# RS232.net
KiCad netlist of a schematic drawn in Altium Designer
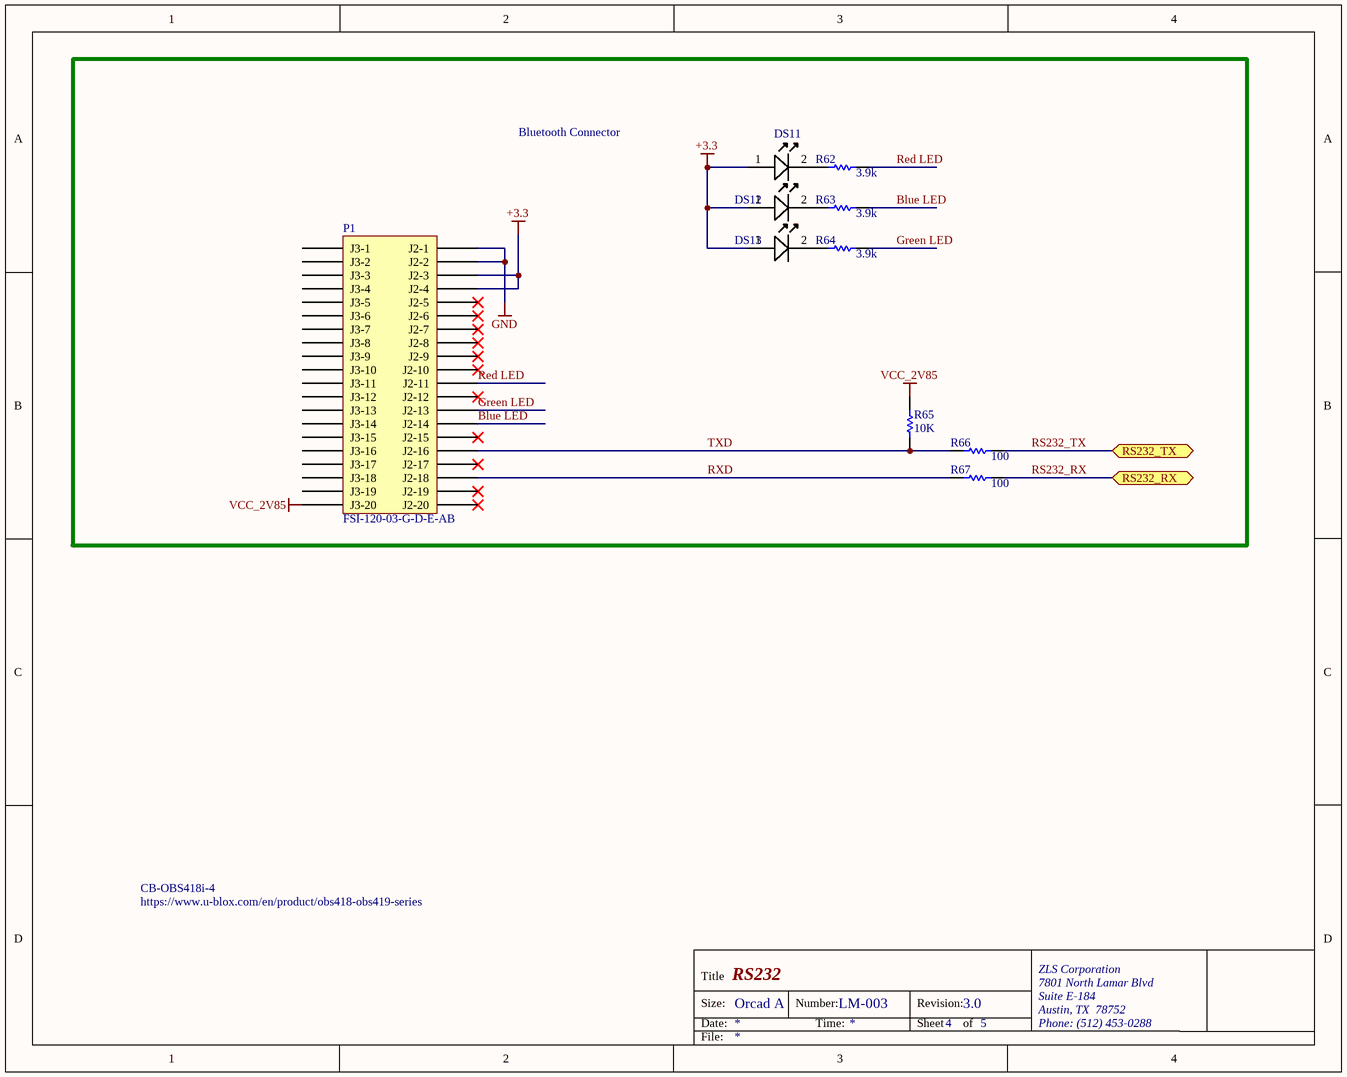
[diagram p0: RS232.SchDoc]

(export (version "E")
  (design (tool "Eeschema 10.0.6"))
  (components
    (comp (ref "DS11")
      (value "Lite-On LTST-S220KGKT Green LED, 571 nm 2012 (0805) Side View, Rectangle Lens SMD package")
      (footprint "0805C_L")
      (fields
        (field (name "MANUFACTURER") "Vishay / Lite-On")
        (field (name "MANUFACTURER PART NUMBER") "LTST-S220KGKT")
      )
      (libsource (lib "*") (part "LED A/K"))
    )
    (comp (ref "DS12")
      (value "Lite-On LTST-S220KGKT Green LED, 571 nm 2012 (0805) Side View, Rectangle Lens SMD package")
      (footprint "0805C_L")
      (fields
        (field (name "MANUFACTURER") "Vishay / Lite-On")
        (field (name "MANUFACTURER PART NUMBER") "LTST-S220KGKT")
      )
      (libsource (lib "*") (part "LED A/K"))
    )
    (comp (ref "DS13")
      (value "Lite-On LTST-S220KGKT Green LED, 571 nm 2012 (0805) Side View, Rectangle Lens SMD package")
      (footprint "0805C_L")
      (fields
        (field (name "MANUFACTURER") "Vishay / Lite-On")
        (field (name "MANUFACTURER PART NUMBER") "LTST-S220KGKT")
      )
      (libsource (lib "*") (part "LED A/K"))
    )
    (comp (ref "P1")
      (value "FSI-120-03-G-D-E-AB")
      (footprint "FSI-120-03-G-D-E-AB")
      (fields (field (name "SUPPLIER PART NUMBER 1") "FSI-120-03-G-D-E-AB"))
      (libsource (lib "ZLS_Schematic_lib") (part "FSI-120-03-G-D-E-AB"))
    )
    (comp (ref "R62")
      (value "3.9k")
      (footprint "RESC0805(2012)_L")
      (description "2R55 0.125W 1% 0805 (2012 Metric)  SMD")
      (fields (field (name "TOLERANCE") "1 %") (field (name "POWER") "0.125 W"))
      (libsource (lib "Altium Content Vault") (part "CMP-1013-00215-1"))
    )
    (comp (ref "R63")
      (value "3.9k")
      (footprint "RESC0805(2012)_L")
      (description "2R55 0.125W 1% 0805 (2012 Metric)  SMD")
      (fields (field (name "TOLERANCE") "1 %") (field (name "POWER") "0.125 W"))
      (libsource (lib "Altium Content Vault") (part "CMP-1013-00215-1"))
    )
    (comp (ref "R64")
      (value "3.9k")
      (footprint "RESC0805(2012)_L")
      (description "2R55 0.125W 1% 0805 (2012 Metric)  SMD")
      (fields (field (name "TOLERANCE") "1 %") (field (name "POWER") "0.125 W"))
      (libsource (lib "Altium Content Vault") (part "CMP-1013-00215-1"))
    )
    (comp (ref "R65")
      (value "10K")
      (footprint "RESC0805(2012)_L")
      (description "2R55 0.125W 1% 0805 (2012 Metric)  SMD")
      (fields (field (name "TOLERANCE") "1 %") (field (name "POWER") "0.125 W"))
      (libsource (lib "Altium Content Vault") (part "CMP-1013-00215-1"))
    )
    (comp (ref "R66")
      (value "100")
      (footprint "RESC0805(2012)_L")
      (description "2R55 0.125W 1% 0805 (2012 Metric)  SMD")
      (fields (field (name "TOLERANCE") "1 %") (field (name "POWER") "0.125 W"))
      (libsource (lib "Altium Content Vault") (part "CMP-1013-00215-1"))
    )
    (comp (ref "R67")
      (value "100")
      (footprint "RESC0805(2012)_L")
      (description "2R55 0.125W 1% 0805 (2012 Metric)  SMD")
      (fields (field (name "TOLERANCE") "1 %") (field (name "POWER") "0.125 W"))
      (libsource (lib "Altium Content Vault") (part "CMP-1013-00215-1"))
    )
  )
  (nets
    (net (code "1") (name "+3.3") (class "Default")
      (node (ref "DS11") (pin "1") (pinfunction "A_1") (pintype "passive"))
      (node (ref "DS12") (pin "1") (pinfunction "A_1") (pintype "passive"))
      (node (ref "DS13") (pin "1") (pinfunction "A_1") (pintype "passive"))
      (node (ref "P1") (pin "J2-3") (pinfunction "J2-3_J2-3") (pintype "passive"))
      (node (ref "P1") (pin "J2-4") (pinfunction "J2-4_J2-4") (pintype "passive"))
    )
    (net (code "2") (name "/Blue LED") (class "Default")
      (node (ref "P1") (pin "J2-14") (pinfunction "J2-14_J2-14") (pintype "passive"))
      (node (ref "R63") (pin "1") (pinfunction "1_1") (pintype "passive"))
    )
    (net (code "3") (name "/Green LED") (class "Default")
      (node (ref "P1") (pin "J2-13") (pinfunction "J2-13_J2-13") (pintype "passive"))
      (node (ref "R64") (pin "1") (pinfunction "1_1") (pintype "passive"))
    )
    (net (code "4") (name "/RS232_RX") (class "Default")
      (node (ref "R67") (pin "1") (pinfunction "1_1") (pintype "passive"))
    )
    (net (code "5") (name "/RS232_TX") (class "Default")
      (node (ref "R66") (pin "1") (pinfunction "1_1") (pintype "passive"))
    )
    (net (code "6") (name "/RXD") (class "Default")
      (node (ref "P1") (pin "J2-18") (pinfunction "J2-18_J2-18") (pintype "passive"))
      (node (ref "R67") (pin "2") (pinfunction "2_2") (pintype "passive"))
    )
    (net (code "7") (name "/Red LED") (class "Default")
      (node (ref "P1") (pin "J2-11") (pinfunction "J2-11_J2-11") (pintype "passive"))
      (node (ref "R62") (pin "1") (pinfunction "1_1") (pintype "passive"))
    )
    (net (code "8") (name "/TXD") (class "Default")
      (node (ref "P1") (pin "J2-16") (pinfunction "J2-16_J2-16") (pintype "passive"))
      (node (ref "R65") (pin "2") (pinfunction "2_2") (pintype "passive"))
      (node (ref "R66") (pin "2") (pinfunction "2_2") (pintype "passive"))
    )
    (net (code "9") (name "GND") (class "Default")
      (node (ref "P1") (pin "J2-1") (pinfunction "J2-1_J2-1") (pintype "passive"))
      (node (ref "P1") (pin "J2-2") (pinfunction "J2-2_J2-2") (pintype "passive"))
    )
    (net (code "10") (name "Net-(DS11-K)") (class "Default")
      (node (ref "DS11") (pin "2") (pinfunction "K_2") (pintype "passive"))
      (node (ref "R62") (pin "2") (pinfunction "2_2") (pintype "passive"))
    )
    (net (code "11") (name "Net-(DS12-K)") (class "Default")
      (node (ref "DS12") (pin "2") (pinfunction "K_2") (pintype "passive"))
      (node (ref "R63") (pin "2") (pinfunction "2_2") (pintype "passive"))
    )
    (net (code "12") (name "Net-(DS13-K)") (class "Default")
      (node (ref "DS13") (pin "2") (pinfunction "K_2") (pintype "passive"))
      (node (ref "R64") (pin "2") (pinfunction "2_2") (pintype "passive"))
    )
    (net (code "13") (name "VCC_2V85") (class "Default")
      (node (ref "P1") (pin "J3-20") (pinfunction "J3-20_J3-20") (pintype "passive"))
      (node (ref "R65") (pin "1") (pinfunction "1_1") (pintype "passive"))
    )
    (net (code "14") (name "unconnected-(P1-PadJ2-5)") (class "Default")
      (node (ref "P1") (pin "J2-5") (pinfunction "J2-5_J2-5") (pintype "passive+no_connect"))
    )
    (net (code "15") (name "unconnected-(P1-PadJ2-6)") (class "Default")
      (node (ref "P1") (pin "J2-6") (pinfunction "J2-6_J2-6") (pintype "passive+no_connect"))
    )
    (net (code "16") (name "unconnected-(P1-PadJ2-7)") (class "Default")
      (node (ref "P1") (pin "J2-7") (pinfunction "J2-7_J2-7") (pintype "passive+no_connect"))
    )
    (net (code "17") (name "unconnected-(P1-PadJ2-8)") (class "Default")
      (node (ref "P1") (pin "J2-8") (pinfunction "J2-8_J2-8") (pintype "passive+no_connect"))
    )
    (net (code "18") (name "unconnected-(P1-PadJ2-9)") (class "Default")
      (node (ref "P1") (pin "J2-9") (pinfunction "J2-9_J2-9") (pintype "passive+no_connect"))
    )
    (net (code "19") (name "unconnected-(P1-PadJ2-10)") (class "Default")
      (node (ref "P1") (pin "J2-10") (pinfunction "J2-10_J2-10") (pintype "passive+no_connect"))
    )
    (net (code "20") (name "unconnected-(P1-PadJ2-12)") (class "Default")
      (node (ref "P1") (pin "J2-12") (pinfunction "J2-12_J2-12") (pintype "passive+no_connect"))
    )
    (net (code "21") (name "unconnected-(P1-PadJ2-15)") (class "Default")
      (node (ref "P1") (pin "J2-15") (pinfunction "J2-15_J2-15") (pintype "passive+no_connect"))
    )
    (net (code "22") (name "unconnected-(P1-PadJ2-17)") (class "Default")
      (node (ref "P1") (pin "J2-17") (pinfunction "J2-17_J2-17") (pintype "passive+no_connect"))
    )
    (net (code "23") (name "unconnected-(P1-PadJ2-19)") (class "Default")
      (node (ref "P1") (pin "J2-19") (pinfunction "J2-19_J2-19") (pintype "passive+no_connect"))
    )
    (net (code "24") (name "unconnected-(P1-PadJ2-20)") (class "Default")
      (node (ref "P1") (pin "J2-20") (pinfunction "J2-20_J2-20") (pintype "passive+no_connect"))
    )
    (net (code "25") (name "unconnected-(P1-PadJ3-1)") (class "Default")
      (node (ref "P1") (pin "J3-1") (pinfunction "J3-1_J3-1") (pintype "passive"))
    )
    (net (code "26") (name "unconnected-(P1-PadJ3-2)") (class "Default")
      (node (ref "P1") (pin "J3-2") (pinfunction "J3-2_J3-2") (pintype "passive"))
    )
    (net (code "27") (name "unconnected-(P1-PadJ3-3)") (class "Default")
      (node (ref "P1") (pin "J3-3") (pinfunction "J3-3_J3-3") (pintype "passive"))
    )
    (net (code "28") (name "unconnected-(P1-PadJ3-4)") (class "Default")
      (node (ref "P1") (pin "J3-4") (pinfunction "J3-4_J3-4") (pintype "passive"))
    )
    (net (code "29") (name "unconnected-(P1-PadJ3-5)") (class "Default")
      (node (ref "P1") (pin "J3-5") (pinfunction "J3-5_J3-5") (pintype "passive"))
    )
    (net (code "30") (name "unconnected-(P1-PadJ3-6)") (class "Default")
      (node (ref "P1") (pin "J3-6") (pinfunction "J3-6_J3-6") (pintype "passive"))
    )
    (net (code "31") (name "unconnected-(P1-PadJ3-7)") (class "Default")
      (node (ref "P1") (pin "J3-7") (pinfunction "J3-7_J3-7") (pintype "passive"))
    )
    (net (code "32") (name "unconnected-(P1-PadJ3-8)") (class "Default")
      (node (ref "P1") (pin "J3-8") (pinfunction "J3-8_J3-8") (pintype "passive"))
    )
    (net (code "33") (name "unconnected-(P1-PadJ3-9)") (class "Default")
      (node (ref "P1") (pin "J3-9") (pinfunction "J3-9_J3-9") (pintype "passive"))
    )
    (net (code "34") (name "unconnected-(P1-PadJ3-10)") (class "Default")
      (node (ref "P1") (pin "J3-10") (pinfunction "J3-10_J3-10") (pintype "passive"))
    )
    (net (code "35") (name "unconnected-(P1-PadJ3-11)") (class "Default")
      (node (ref "P1") (pin "J3-11") (pinfunction "J3-11_J3-11") (pintype "passive"))
    )
    (net (code "36") (name "unconnected-(P1-PadJ3-12)") (class "Default")
      (node (ref "P1") (pin "J3-12") (pinfunction "J3-12_J3-12") (pintype "passive"))
    )
    (net (code "37") (name "unconnected-(P1-PadJ3-13)") (class "Default")
      (node (ref "P1") (pin "J3-13") (pinfunction "J3-13_J3-13") (pintype "passive"))
    )
    (net (code "38") (name "unconnected-(P1-PadJ3-14)") (class "Default")
      (node (ref "P1") (pin "J3-14") (pinfunction "J3-14_J3-14") (pintype "passive"))
    )
    (net (code "39") (name "unconnected-(P1-PadJ3-15)") (class "Default")
      (node (ref "P1") (pin "J3-15") (pinfunction "J3-15_J3-15") (pintype "passive"))
    )
    (net (code "40") (name "unconnected-(P1-PadJ3-16)") (class "Default")
      (node (ref "P1") (pin "J3-16") (pinfunction "J3-16_J3-16") (pintype "passive"))
    )
    (net (code "41") (name "unconnected-(P1-PadJ3-17)") (class "Default")
      (node (ref "P1") (pin "J3-17") (pinfunction "J3-17_J3-17") (pintype "passive"))
    )
    (net (code "42") (name "unconnected-(P1-PadJ3-18)") (class "Default")
      (node (ref "P1") (pin "J3-18") (pinfunction "J3-18_J3-18") (pintype "passive"))
    )
    (net (code "43") (name "unconnected-(P1-PadJ3-19)") (class "Default")
      (node (ref "P1") (pin "J3-19") (pinfunction "J3-19_J3-19") (pintype "passive"))
    )
  )
)
